# minimumSystem_Fachrur_Rozi_21507334051.net
KiCad netlist of a schematic drawn in EAGLE
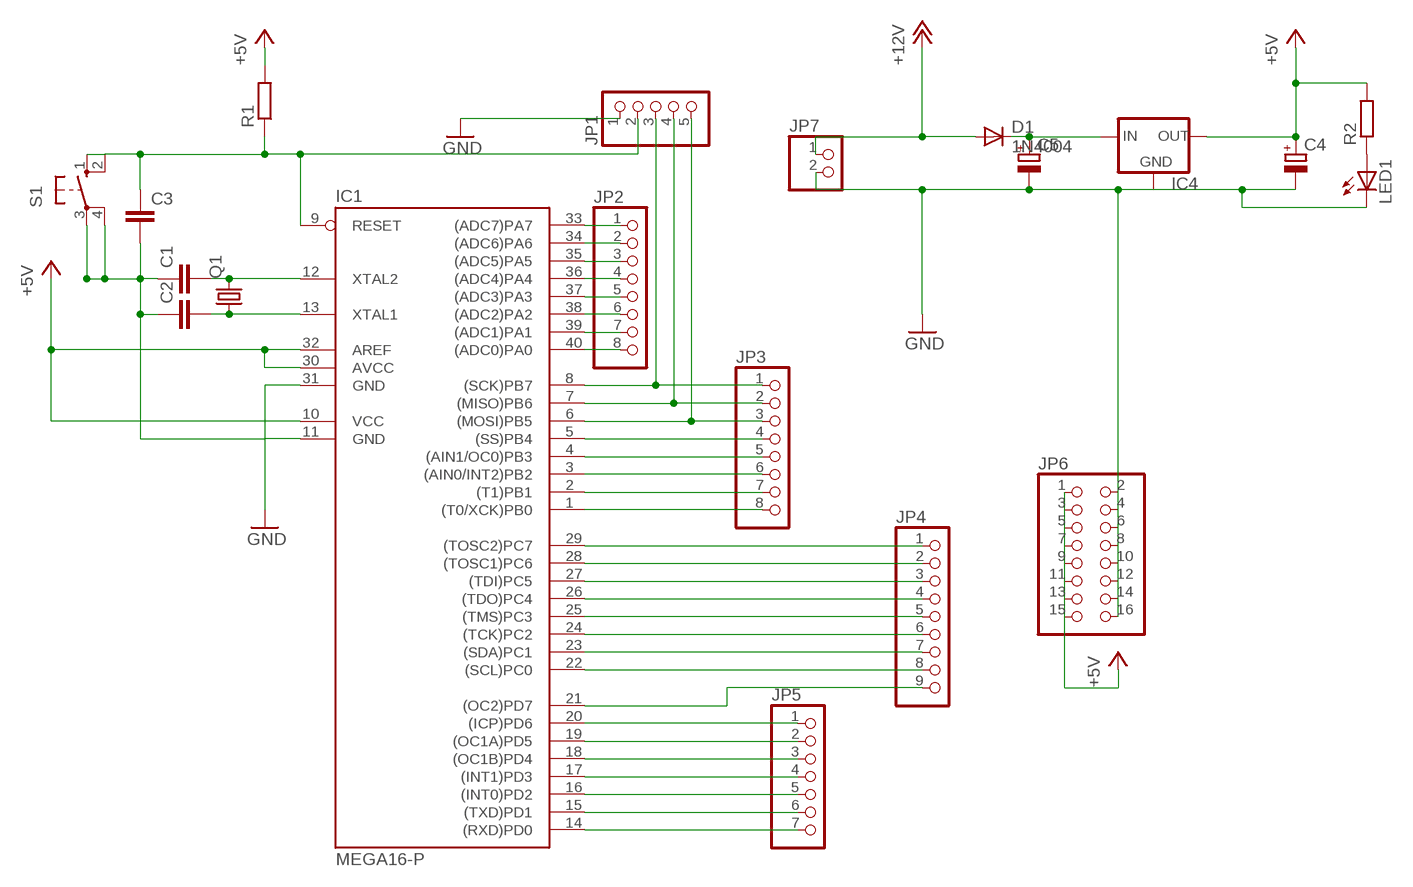
[diagram p0: schematic, sheet 1]

(export (version "E")
  (design (tool "Eeschema 10.0.6"))
  (components
    (comp (ref "C1")
      (value "C-EU025-024X044")
      (footprint "eagle-import:C025-024X044")
      (libsource (lib "eagle-import") (part "C-EU025-024X044"))
    )
    (comp (ref "C2")
      (value "C-EU025-024X044")
      (footprint "eagle-import:C025-024X044")
      (libsource (lib "eagle-import") (part "C-EU025-024X044"))
    )
    (comp (ref "C3")
      (value "C-EU050-025X075")
      (footprint "eagle-import:C050-025X075")
      (libsource (lib "eagle-import") (part "resistor_C-EU050-025X075"))
    )
    (comp (ref "C4")
      (value "CPOL-EUE2.5-5")
      (footprint "eagle-import:E2,5-5")
      (libsource (lib "eagle-import") (part "CPOL-EUE2.5-5"))
    )
    (comp (ref "C5")
      (value "CPOL-EUE2.5-5")
      (footprint "eagle-import:E2,5-5")
      (libsource (lib "eagle-import") (part "CPOL-EUE2.5-5"))
    )
    (comp (ref "D1")
      (value "1N4004")
      (footprint "eagle-import:DO41-10")
      (libsource (lib "eagle-import") (part "1N4004"))
    )
    (comp (ref "IC1")
      (value "MEGA16-P")
      (footprint "eagle-import:DIL40")
      (fields (field (name "MPN") "ATMEGA16-16PU"))
      (libsource (lib "eagle-import") (part "MEGA16-P"))
    )
    (comp (ref "IC4")
      (value "78XXS")
      (footprint "eagle-import:78XXS")
      (libsource (lib "eagle-import") (part "78XXS"))
    )
    (comp (ref "JP1")
      (value "PINHD-1X5")
      (footprint "eagle-import:1X05")
      (libsource (lib "eagle-import") (part "PINHD-1X5"))
    )
    (comp (ref "JP2")
      (value "PINHD-1X8")
      (footprint "eagle-import:1X08")
      (libsource (lib "eagle-import") (part "PINHD-1X8"))
    )
    (comp (ref "JP3")
      (value "PINHD-1X8")
      (footprint "eagle-import:1X08")
      (libsource (lib "eagle-import") (part "PINHD-1X8"))
    )
    (comp (ref "JP4")
      (value "PINHD-1X9")
      (footprint "eagle-import:1X09")
      (libsource (lib "eagle-import") (part "PINHD-1X9"))
    )
    (comp (ref "JP5")
      (value "PINHD-1X7")
      (footprint "eagle-import:1X07")
      (libsource (lib "eagle-import") (part "PINHD-1X7"))
    )
    (comp (ref "JP6")
      (value "PINHD-2X8")
      (footprint "eagle-import:2X08")
      (libsource (lib "eagle-import") (part "PINHD-2X8"))
    )
    (comp (ref "JP7")
      (value "PINHD-1X2")
      (footprint "eagle-import:1X02")
      (libsource (lib "eagle-import") (part "PINHD-1X2"))
    )
    (comp (ref "LED1")
      (value "LED5MM")
      (footprint "eagle-import:LED5MM")
      (libsource (lib "eagle-import") (part "LED5MM"))
    )
    (comp (ref "Q1")
      (value "CRYSTALHC49U-V")
      (footprint "eagle-import:HC49U-V")
      (libsource (lib "eagle-import") (part "CRYSTALHC49U-V"))
    )
    (comp (ref "R1")
      (value "R-EU_0204/7")
      (footprint "eagle-import:0204_7")
      (libsource (lib "eagle-import") (part "R-EU_0204/7"))
    )
    (comp (ref "R2")
      (value "R-EU_0204/7")
      (footprint "eagle-import:0204_7")
      (libsource (lib "eagle-import") (part "R-EU_0204/7"))
    )
    (comp (ref "S1")
      (value "10-XX")
      (footprint "eagle-import:B3F-10XX")
      (fields (field (name "MPN") "B3F-1000"))
      (libsource (lib "eagle-import") (part "10-XX"))
    )
  )
  (nets
    (net (code "1") (name "+5V") (class "Default")
      (node (ref "C4") (pin "+") (pinfunction "+_+") (pintype "passive"))
      (node (ref "IC1") (pin "10") (pinfunction "VCC_10") (pintype "power_in"))
      (node (ref "IC1") (pin "30") (pinfunction "AVCC_30") (pintype "power_in"))
      (node (ref "IC1") (pin "32") (pinfunction "AREF_32") (pintype "passive"))
      (node (ref "IC4") (pin "OUT") (pinfunction "OUT_OUT") (pintype "passive"))
      (node (ref "JP6") (pin "1") (pinfunction "1_1") (pintype "passive"))
      (node (ref "JP6") (pin "11") (pinfunction "11_11") (pintype "passive"))
      (node (ref "JP6") (pin "13") (pinfunction "13_13") (pintype "passive"))
      (node (ref "JP6") (pin "15") (pinfunction "15_15") (pintype "passive"))
      (node (ref "JP6") (pin "3") (pinfunction "3_3") (pintype "passive"))
      (node (ref "JP6") (pin "5") (pinfunction "5_5") (pintype "passive"))
      (node (ref "JP6") (pin "7") (pinfunction "7_7") (pintype "passive"))
      (node (ref "JP6") (pin "9") (pinfunction "9_9") (pintype "passive"))
      (node (ref "R1") (pin "2") (pinfunction "2_2") (pintype "passive"))
      (node (ref "R2") (pin "2") (pinfunction "2_2") (pintype "passive"))
    )
    (net (code "2") (name "+12V") (class "Default")
      (node (ref "D1") (pin "A") (pinfunction "A_A") (pintype "passive"))
      (node (ref "JP7") (pin "1") (pinfunction "1_1") (pintype "passive"))
    )
    (net (code "3") (name "GND") (class "Default")
      (node (ref "C1") (pin "1") (pinfunction "1_1") (pintype "passive"))
      (node (ref "C2") (pin "1") (pinfunction "1_1") (pintype "passive"))
      (node (ref "C3") (pin "2") (pinfunction "2_2") (pintype "passive"))
      (node (ref "C4") (pin "-") (pinfunction "-_-") (pintype "passive"))
      (node (ref "C5") (pin "-") (pinfunction "-_-") (pintype "passive"))
      (node (ref "IC1") (pin "11") (pinfunction "GND_11") (pintype "power_in"))
      (node (ref "IC1") (pin "31") (pinfunction "GND_31") (pintype "power_in"))
      (node (ref "IC4") (pin "GND") (pinfunction "GND_GND") (pintype "input"))
      (node (ref "JP1") (pin "1") (pinfunction "1_1") (pintype "passive"))
      (node (ref "JP6") (pin "10") (pinfunction "10_10") (pintype "passive"))
      (node (ref "JP6") (pin "12") (pinfunction "12_12") (pintype "passive"))
      (node (ref "JP6") (pin "14") (pinfunction "14_14") (pintype "passive"))
      (node (ref "JP6") (pin "16") (pinfunction "16_16") (pintype "passive"))
      (node (ref "JP6") (pin "2") (pinfunction "2_2") (pintype "passive"))
      (node (ref "JP6") (pin "4") (pinfunction "4_4") (pintype "passive"))
      (node (ref "JP6") (pin "6") (pinfunction "6_6") (pintype "passive"))
      (node (ref "JP6") (pin "8") (pinfunction "8_8") (pintype "passive"))
      (node (ref "JP7") (pin "2") (pinfunction "2_2") (pintype "passive"))
      (node (ref "LED1") (pin "K") (pinfunction "C_K") (pintype "passive"))
      (node (ref "S1") (pin "3") (pinfunction "P_3") (pintype "passive"))
      (node (ref "S1") (pin "4") (pinfunction "P1_4") (pintype "passive"))
    )
    (net (code "4") (name "Net-(C5-Pad+)") (class "Default")
      (node (ref "C5") (pin "+") (pinfunction "+_+") (pintype "passive"))
      (node (ref "D1") (pin "C") (pinfunction "C_C") (pintype "passive"))
      (node (ref "IC4") (pin "IN") (pinfunction "IN_IN") (pintype "input"))
    )
    (net (code "5") (name "Net-(IC1-(ADC0)PA0)") (class "Default")
      (node (ref "IC1") (pin "40") (pinfunction "(ADC0)PA0_40") (pintype "bidirectional"))
      (node (ref "JP2") (pin "8") (pinfunction "8_8") (pintype "passive"))
    )
    (net (code "6") (name "Net-(IC1-(ADC1)PA1)") (class "Default")
      (node (ref "IC1") (pin "39") (pinfunction "(ADC1)PA1_39") (pintype "bidirectional"))
      (node (ref "JP2") (pin "7") (pinfunction "7_7") (pintype "passive"))
    )
    (net (code "7") (name "Net-(IC1-(ADC2)PA2)") (class "Default")
      (node (ref "IC1") (pin "38") (pinfunction "(ADC2)PA2_38") (pintype "bidirectional"))
      (node (ref "JP2") (pin "6") (pinfunction "6_6") (pintype "passive"))
    )
    (net (code "8") (name "Net-(IC1-(ADC3)PA3)") (class "Default")
      (node (ref "IC1") (pin "37") (pinfunction "(ADC3)PA3_37") (pintype "bidirectional"))
      (node (ref "JP2") (pin "5") (pinfunction "5_5") (pintype "passive"))
    )
    (net (code "9") (name "Net-(IC1-(ADC4)PA4)") (class "Default")
      (node (ref "IC1") (pin "36") (pinfunction "(ADC4)PA4_36") (pintype "bidirectional"))
      (node (ref "JP2") (pin "4") (pinfunction "4_4") (pintype "passive"))
    )
    (net (code "10") (name "Net-(IC1-(ADC5)PA5)") (class "Default")
      (node (ref "IC1") (pin "35") (pinfunction "(ADC5)PA5_35") (pintype "bidirectional"))
      (node (ref "JP2") (pin "3") (pinfunction "3_3") (pintype "passive"))
    )
    (net (code "11") (name "Net-(IC1-(ADC6)PA6)") (class "Default")
      (node (ref "IC1") (pin "34") (pinfunction "(ADC6)PA6_34") (pintype "bidirectional"))
      (node (ref "JP2") (pin "2") (pinfunction "2_2") (pintype "passive"))
    )
    (net (code "12") (name "Net-(IC1-(ADC7)PA7)") (class "Default")
      (node (ref "IC1") (pin "33") (pinfunction "(ADC7)PA7_33") (pintype "bidirectional"))
      (node (ref "JP2") (pin "1") (pinfunction "1_1") (pintype "passive"))
    )
    (net (code "13") (name "Net-(IC1-(AIN0{slash}INT2)PB2)") (class "Default")
      (node (ref "IC1") (pin "3") (pinfunction "(AIN0/INT2)PB2_3") (pintype "bidirectional"))
      (node (ref "JP3") (pin "6") (pinfunction "6_6") (pintype "passive"))
    )
    (net (code "14") (name "Net-(IC1-(AIN1{slash}OC0)PB3)") (class "Default")
      (node (ref "IC1") (pin "4") (pinfunction "(AIN1/OC0)PB3_4") (pintype "bidirectional"))
      (node (ref "JP3") (pin "5") (pinfunction "5_5") (pintype "passive"))
    )
    (net (code "15") (name "Net-(IC1-(ICP)PD6)") (class "Default")
      (node (ref "IC1") (pin "20") (pinfunction "(ICP)PD6_20") (pintype "bidirectional"))
      (node (ref "JP5") (pin "1") (pinfunction "1_1") (pintype "passive"))
    )
    (net (code "16") (name "Net-(IC1-(INT0)PD2)") (class "Default")
      (node (ref "IC1") (pin "16") (pinfunction "(INT0)PD2_16") (pintype "bidirectional"))
      (node (ref "JP5") (pin "5") (pinfunction "5_5") (pintype "passive"))
    )
    (net (code "17") (name "Net-(IC1-(INT1)PD3)") (class "Default")
      (node (ref "IC1") (pin "17") (pinfunction "(INT1)PD3_17") (pintype "bidirectional"))
      (node (ref "JP5") (pin "4") (pinfunction "4_4") (pintype "passive"))
    )
    (net (code "18") (name "Net-(IC1-(MISO)PB6)") (class "Default")
      (node (ref "IC1") (pin "7") (pinfunction "(MISO)PB6_7") (pintype "bidirectional"))
      (node (ref "JP1") (pin "4") (pinfunction "4_4") (pintype "passive"))
      (node (ref "JP3") (pin "2") (pinfunction "2_2") (pintype "passive"))
    )
    (net (code "19") (name "Net-(IC1-(MOSI)PB5)") (class "Default")
      (node (ref "IC1") (pin "6") (pinfunction "(MOSI)PB5_6") (pintype "bidirectional"))
      (node (ref "JP1") (pin "5") (pinfunction "5_5") (pintype "passive"))
      (node (ref "JP3") (pin "3") (pinfunction "3_3") (pintype "passive"))
    )
    (net (code "20") (name "Net-(IC1-(OC1A)PD5)") (class "Default")
      (node (ref "IC1") (pin "19") (pinfunction "(OC1A)PD5_19") (pintype "bidirectional"))
      (node (ref "JP5") (pin "2") (pinfunction "2_2") (pintype "passive"))
    )
    (net (code "21") (name "Net-(IC1-(OC1B)PD4)") (class "Default")
      (node (ref "IC1") (pin "18") (pinfunction "(OC1B)PD4_18") (pintype "bidirectional"))
      (node (ref "JP5") (pin "3") (pinfunction "3_3") (pintype "passive"))
    )
    (net (code "22") (name "Net-(IC1-(OC2)PD7)") (class "Default")
      (node (ref "IC1") (pin "21") (pinfunction "(OC2)PD7_21") (pintype "bidirectional"))
      (node (ref "JP4") (pin "9") (pinfunction "9_9") (pintype "passive"))
    )
    (net (code "23") (name "Net-(IC1-(RXD)PD0)") (class "Default")
      (node (ref "IC1") (pin "14") (pinfunction "(RXD)PD0_14") (pintype "bidirectional"))
      (node (ref "JP5") (pin "7") (pinfunction "7_7") (pintype "passive"))
    )
    (net (code "24") (name "Net-(IC1-(SCK)PB7)") (class "Default")
      (node (ref "IC1") (pin "8") (pinfunction "(SCK)PB7_8") (pintype "bidirectional"))
      (node (ref "JP1") (pin "3") (pinfunction "3_3") (pintype "passive"))
      (node (ref "JP3") (pin "1") (pinfunction "1_1") (pintype "passive"))
    )
    (net (code "25") (name "Net-(IC1-(SCL)PC0)") (class "Default")
      (node (ref "IC1") (pin "22") (pinfunction "(SCL)PC0_22") (pintype "bidirectional"))
      (node (ref "JP4") (pin "8") (pinfunction "8_8") (pintype "passive"))
    )
    (net (code "26") (name "Net-(IC1-(SDA)PC1)") (class "Default")
      (node (ref "IC1") (pin "23") (pinfunction "(SDA)PC1_23") (pintype "bidirectional"))
      (node (ref "JP4") (pin "7") (pinfunction "7_7") (pintype "passive"))
    )
    (net (code "27") (name "Net-(IC1-(SS)PB4)") (class "Default")
      (node (ref "IC1") (pin "5") (pinfunction "(SS)PB4_5") (pintype "bidirectional"))
      (node (ref "JP3") (pin "4") (pinfunction "4_4") (pintype "passive"))
    )
    (net (code "28") (name "Net-(IC1-(T0{slash}XCK)PB0)") (class "Default")
      (node (ref "IC1") (pin "1") (pinfunction "(T0/XCK)PB0_1") (pintype "bidirectional"))
      (node (ref "JP3") (pin "8") (pinfunction "8_8") (pintype "passive"))
    )
    (net (code "29") (name "Net-(IC1-(T1)PB1)") (class "Default")
      (node (ref "IC1") (pin "2") (pinfunction "(T1)PB1_2") (pintype "bidirectional"))
      (node (ref "JP3") (pin "7") (pinfunction "7_7") (pintype "passive"))
    )
    (net (code "30") (name "Net-(IC1-(TCK)PC2)") (class "Default")
      (node (ref "IC1") (pin "24") (pinfunction "(TCK)PC2_24") (pintype "bidirectional"))
      (node (ref "JP4") (pin "6") (pinfunction "6_6") (pintype "passive"))
    )
    (net (code "31") (name "Net-(IC1-(TDI)PC5)") (class "Default")
      (node (ref "IC1") (pin "27") (pinfunction "(TDI)PC5_27") (pintype "bidirectional"))
      (node (ref "JP4") (pin "3") (pinfunction "3_3") (pintype "passive"))
    )
    (net (code "32") (name "Net-(IC1-(TDO)PC4)") (class "Default")
      (node (ref "IC1") (pin "26") (pinfunction "(TDO)PC4_26") (pintype "bidirectional"))
      (node (ref "JP4") (pin "4") (pinfunction "4_4") (pintype "passive"))
    )
    (net (code "33") (name "Net-(IC1-(TMS)PC3)") (class "Default")
      (node (ref "IC1") (pin "25") (pinfunction "(TMS)PC3_25") (pintype "bidirectional"))
      (node (ref "JP4") (pin "5") (pinfunction "5_5") (pintype "passive"))
    )
    (net (code "34") (name "Net-(IC1-(TOSC1)PC6)") (class "Default")
      (node (ref "IC1") (pin "28") (pinfunction "(TOSC1)PC6_28") (pintype "bidirectional"))
      (node (ref "JP4") (pin "2") (pinfunction "2_2") (pintype "passive"))
    )
    (net (code "35") (name "Net-(IC1-(TOSC2)PC7)") (class "Default")
      (node (ref "IC1") (pin "29") (pinfunction "(TOSC2)PC7_29") (pintype "bidirectional"))
      (node (ref "JP4") (pin "1") (pinfunction "1_1") (pintype "passive"))
    )
    (net (code "36") (name "Net-(IC1-(TXD)PD1)") (class "Default")
      (node (ref "IC1") (pin "15") (pinfunction "(TXD)PD1_15") (pintype "bidirectional"))
      (node (ref "JP5") (pin "6") (pinfunction "6_6") (pintype "passive"))
    )
    (net (code "37") (name "Net-(IC1-RESET)") (class "Default")
      (node (ref "C3") (pin "1") (pinfunction "1_1") (pintype "passive"))
      (node (ref "IC1") (pin "9") (pinfunction "RESET_9") (pintype "input"))
      (node (ref "JP1") (pin "2") (pinfunction "2_2") (pintype "passive"))
      (node (ref "R1") (pin "1") (pinfunction "1_1") (pintype "passive"))
      (node (ref "S1") (pin "1") (pinfunction "S_1") (pintype "passive"))
      (node (ref "S1") (pin "2") (pinfunction "S1_2") (pintype "passive"))
    )
    (net (code "38") (name "Net-(IC1-XTAL1)") (class "Default")
      (node (ref "C2") (pin "2") (pinfunction "2_2") (pintype "passive"))
      (node (ref "IC1") (pin "13") (pinfunction "XTAL1_13") (pintype "bidirectional"))
      (node (ref "Q1") (pin "1") (pinfunction "1_1") (pintype "passive"))
    )
    (net (code "39") (name "Net-(IC1-XTAL2)") (class "Default")
      (node (ref "C1") (pin "2") (pinfunction "2_2") (pintype "passive"))
      (node (ref "IC1") (pin "12") (pinfunction "XTAL2_12") (pintype "bidirectional"))
      (node (ref "Q1") (pin "2") (pinfunction "2_2") (pintype "passive"))
    )
    (net (code "40") (name "Net-(LED1-PadA)") (class "Default")
      (node (ref "LED1") (pin "A") (pinfunction "A_A") (pintype "passive"))
      (node (ref "R2") (pin "1") (pinfunction "1_1") (pintype "passive"))
    )
  )
)
